# main.net
KiCad netlist of a schematic drawn in Altium Designer
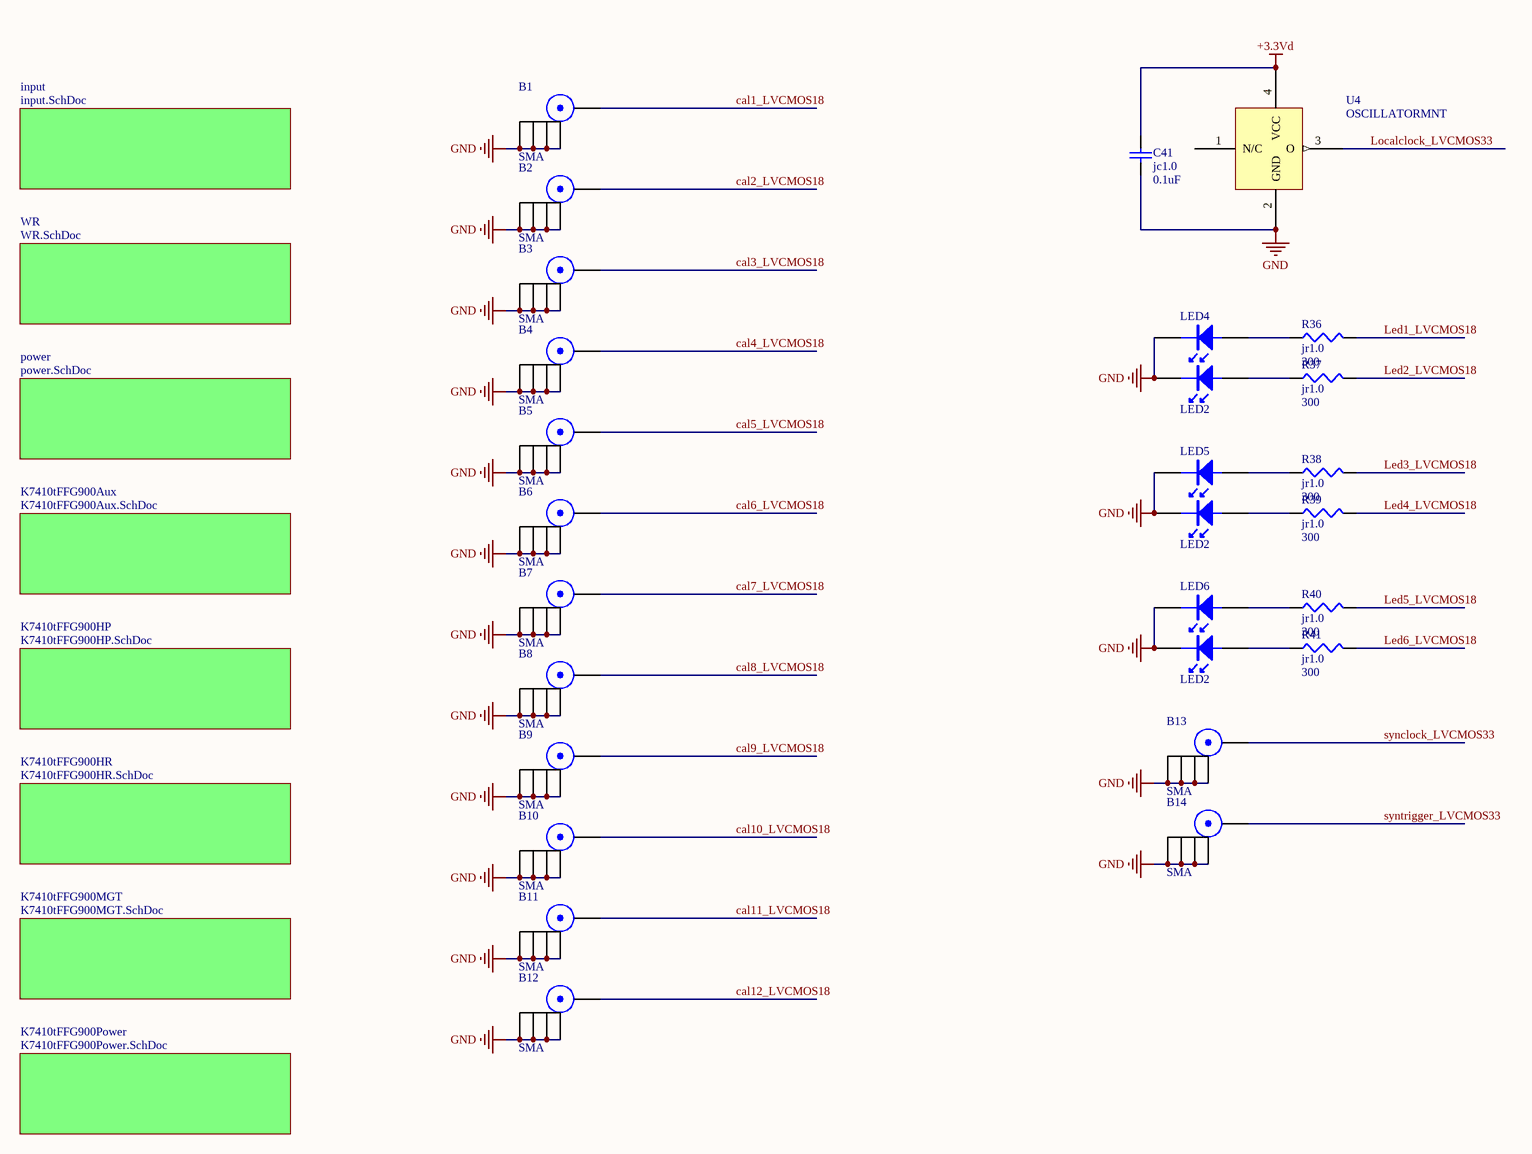
[diagram p0: main.SchDoc]

(export (version "E")
  (design (tool "Eeschema 10.0.6"))
  (components
    (comp (ref "B1") (value "SMA") (footprint "SMA_2") (libsource (lib "LIB01DXP2006SchLib") (part "SMA")))
    (comp (ref "B2") (value "SMA") (footprint "SMA_2") (libsource (lib "LIB01DXP2006SchLib") (part "SMA")))
    (comp (ref "B3") (value "SMA") (footprint "SMA_2") (libsource (lib "LIB01DXP2006SchLib") (part "SMA")))
    (comp (ref "B4") (value "SMA") (footprint "SMA_2") (libsource (lib "LIB01DXP2006SchLib") (part "SMA")))
    (comp (ref "B5") (value "SMA") (footprint "SMA_2") (libsource (lib "LIB01DXP2006SchLib") (part "SMA")))
    (comp (ref "B6") (value "SMA") (footprint "SMA_2") (libsource (lib "LIB01DXP2006SchLib") (part "SMA")))
    (comp (ref "B7") (value "SMA") (footprint "SMA_2") (libsource (lib "LIB01DXP2006SchLib") (part "SMA")))
    (comp (ref "B8") (value "SMA") (footprint "SMA_2") (libsource (lib "LIB01DXP2006SchLib") (part "SMA")))
    (comp (ref "B9") (value "SMA") (footprint "SMA_2") (libsource (lib "LIB01DXP2006SchLib") (part "SMA")))
    (comp (ref "B10") (value "SMA") (footprint "SMA_2") (libsource (lib "LIB01DXP2006SchLib") (part "SMA")))
    (comp (ref "B11") (value "SMA") (footprint "SMA_2") (libsource (lib "LIB01DXP2006SchLib") (part "SMA")))
    (comp (ref "B12") (value "SMA") (footprint "SMA_2") (libsource (lib "LIB01DXP2006SchLib") (part "SMA")))
    (comp (ref "B13") (value "SMA") (footprint "SMA_2") (libsource (lib "LIB01DXP2006SchLib") (part "SMA")))
    (comp (ref "B14") (value "SMA") (footprint "SMA_2") (libsource (lib "LIB01DXP2006SchLib") (part "SMA")))
    (comp (ref "C41")
      (value "jc1.0")
      (footprint "0603")
      (description "Capacitor")
      (fields (field (name "ALTIUM_VALUE") "0.1uF") (field (name "PUBLISHER") "Altium Limited"))
      (libsource (lib "LIB01DXP2006SchLib") (part "Cap"))
    )
    (comp (ref "LED4") (value "LED2") (footprint "LED2") (libsource (lib "LIB01DXP2006SchLib") (part "LED2")))
    (comp (ref "LED5") (value "LED2") (footprint "LED2") (libsource (lib "LIB01DXP2006SchLib") (part "LED2")))
    (comp (ref "LED6") (value "LED2") (footprint "LED2") (libsource (lib "LIB01DXP2006SchLib") (part "LED2")))
    (comp (ref "R36")
      (value "jr1.0")
      (footprint "0805")
      (description "Resistor")
      (fields (field (name "ALTIUM_VALUE") "300") (field (name "PUBLISHER") "Altium Limited"))
      (libsource (lib "LIB01DXP2006SchLib") (part "Res"))
    )
    (comp (ref "R37")
      (value "jr1.0")
      (footprint "0805")
      (description "Resistor")
      (fields (field (name "ALTIUM_VALUE") "300") (field (name "PUBLISHER") "Altium Limited"))
      (libsource (lib "LIB01DXP2006SchLib") (part "Res"))
    )
    (comp (ref "R38")
      (value "jr1.0")
      (footprint "0805")
      (description "Resistor")
      (fields (field (name "ALTIUM_VALUE") "300") (field (name "PUBLISHER") "Altium Limited"))
      (libsource (lib "LIB01DXP2006SchLib") (part "Res"))
    )
    (comp (ref "R39")
      (value "jr1.0")
      (footprint "0805")
      (description "Resistor")
      (fields (field (name "ALTIUM_VALUE") "300") (field (name "PUBLISHER") "Altium Limited"))
      (libsource (lib "LIB01DXP2006SchLib") (part "Res"))
    )
    (comp (ref "R40")
      (value "jr1.0")
      (footprint "0805")
      (description "Resistor")
      (fields (field (name "ALTIUM_VALUE") "300") (field (name "PUBLISHER") "Altium Limited"))
      (libsource (lib "LIB01DXP2006SchLib") (part "Res"))
    )
    (comp (ref "R41")
      (value "jr1.0")
      (footprint "0805")
      (description "Resistor")
      (fields (field (name "ALTIUM_VALUE") "300") (field (name "PUBLISHER") "Altium Limited"))
      (libsource (lib "LIB01DXP2006SchLib") (part "Res"))
    )
    (comp (ref "U4")
      (value "OSCILLATORMNT")
      (footprint "S11")
      (libsource (lib "LIB01DXP2006SchLib") (part "OSCILLATOR"))
    )
  )
  (nets
    (net (code "1") (name "+3.3Vd") (class "Default")
      (node (ref "C41") (pin "2") (pinfunction "2_2") (pintype "passive"))
      (node (ref "U4") (pin "4") (pinfunction "VCC_4") (pintype "power_in"))
    )
    (net (code "2") (name "/Led1_LVCMOS18") (class "Default")
      (node (ref "R36") (pin "2") (pinfunction "2_2") (pintype "passive"))
    )
    (net (code "3") (name "/Led2_LVCMOS18") (class "Default")
      (node (ref "R37") (pin "2") (pinfunction "2_2") (pintype "passive"))
    )
    (net (code "4") (name "/Led3_LVCMOS18") (class "Default")
      (node (ref "R38") (pin "2") (pinfunction "2_2") (pintype "passive"))
    )
    (net (code "5") (name "/Led4_LVCMOS18") (class "Default")
      (node (ref "R39") (pin "2") (pinfunction "2_2") (pintype "passive"))
    )
    (net (code "6") (name "/Led5_LVCMOS18") (class "Default")
      (node (ref "R40") (pin "2") (pinfunction "2_2") (pintype "passive"))
    )
    (net (code "7") (name "/Led6_LVCMOS18") (class "Default")
      (node (ref "R41") (pin "2") (pinfunction "2_2") (pintype "passive"))
    )
    (net (code "8") (name "/Localclock_LVCMOS33") (class "Default")
      (node (ref "U4") (pin "3") (pinfunction "O_3") (pintype "output"))
    )
    (net (code "9") (name "/cal1_LVCMOS18") (class "Default")
      (node (ref "B1") (pin "1") (pinfunction "X_1") (pintype "passive"))
    )
    (net (code "10") (name "/cal2_LVCMOS18") (class "Default")
      (node (ref "B2") (pin "1") (pinfunction "X_1") (pintype "passive"))
    )
    (net (code "11") (name "/cal3_LVCMOS18") (class "Default")
      (node (ref "B3") (pin "1") (pinfunction "X_1") (pintype "passive"))
    )
    (net (code "12") (name "/cal4_LVCMOS18") (class "Default")
      (node (ref "B4") (pin "1") (pinfunction "X_1") (pintype "passive"))
    )
    (net (code "13") (name "/cal5_LVCMOS18") (class "Default")
      (node (ref "B5") (pin "1") (pinfunction "X_1") (pintype "passive"))
    )
    (net (code "14") (name "/cal6_LVCMOS18") (class "Default")
      (node (ref "B6") (pin "1") (pinfunction "X_1") (pintype "passive"))
    )
    (net (code "15") (name "/cal7_LVCMOS18") (class "Default")
      (node (ref "B7") (pin "1") (pinfunction "X_1") (pintype "passive"))
    )
    (net (code "16") (name "/cal8_LVCMOS18") (class "Default")
      (node (ref "B8") (pin "1") (pinfunction "X_1") (pintype "passive"))
    )
    (net (code "17") (name "/cal9_LVCMOS18") (class "Default")
      (node (ref "B9") (pin "1") (pinfunction "X_1") (pintype "passive"))
    )
    (net (code "18") (name "/cal10_LVCMOS18") (class "Default")
      (node (ref "B10") (pin "1") (pinfunction "X_1") (pintype "passive"))
    )
    (net (code "19") (name "/cal11_LVCMOS18") (class "Default")
      (node (ref "B11") (pin "1") (pinfunction "X_1") (pintype "passive"))
    )
    (net (code "20") (name "/cal12_LVCMOS18") (class "Default")
      (node (ref "B12") (pin "1") (pinfunction "X_1") (pintype "passive"))
    )
    (net (code "21") (name "/synclock_LVCMOS33") (class "Default")
      (node (ref "B13") (pin "1") (pinfunction "X_1") (pintype "passive"))
    )
    (net (code "22") (name "/syntrigger_LVCMOS33") (class "Default")
      (node (ref "B14") (pin "1") (pinfunction "X_1") (pintype "passive"))
    )
    (net (code "23") (name "GND") (class "Default")
      (node (ref "B1") (pin "2") (pinfunction "GND_2") (pintype "passive"))
      (node (ref "B1") (pin "3") (pinfunction "GND_3") (pintype "passive"))
      (node (ref "B1") (pin "4") (pinfunction "GND_4") (pintype "passive"))
      (node (ref "B1") (pin "5") (pinfunction "GND_5") (pintype "passive"))
      (node (ref "B10") (pin "2") (pinfunction "GND_2") (pintype "passive"))
      (node (ref "B10") (pin "3") (pinfunction "GND_3") (pintype "passive"))
      (node (ref "B10") (pin "4") (pinfunction "GND_4") (pintype "passive"))
      (node (ref "B10") (pin "5") (pinfunction "GND_5") (pintype "passive"))
      (node (ref "B11") (pin "2") (pinfunction "GND_2") (pintype "passive"))
      (node (ref "B11") (pin "3") (pinfunction "GND_3") (pintype "passive"))
      (node (ref "B11") (pin "4") (pinfunction "GND_4") (pintype "passive"))
      (node (ref "B11") (pin "5") (pinfunction "GND_5") (pintype "passive"))
      (node (ref "B12") (pin "2") (pinfunction "GND_2") (pintype "passive"))
      (node (ref "B12") (pin "3") (pinfunction "GND_3") (pintype "passive"))
      (node (ref "B12") (pin "4") (pinfunction "GND_4") (pintype "passive"))
      (node (ref "B12") (pin "5") (pinfunction "GND_5") (pintype "passive"))
      (node (ref "B13") (pin "2") (pinfunction "GND_2") (pintype "passive"))
      (node (ref "B13") (pin "3") (pinfunction "GND_3") (pintype "passive"))
      (node (ref "B13") (pin "4") (pinfunction "GND_4") (pintype "passive"))
      (node (ref "B13") (pin "5") (pinfunction "GND_5") (pintype "passive"))
      (node (ref "B14") (pin "2") (pinfunction "GND_2") (pintype "passive"))
      (node (ref "B14") (pin "3") (pinfunction "GND_3") (pintype "passive"))
      (node (ref "B14") (pin "4") (pinfunction "GND_4") (pintype "passive"))
      (node (ref "B14") (pin "5") (pinfunction "GND_5") (pintype "passive"))
      (node (ref "B2") (pin "2") (pinfunction "GND_2") (pintype "passive"))
      (node (ref "B2") (pin "3") (pinfunction "GND_3") (pintype "passive"))
      (node (ref "B2") (pin "4") (pinfunction "GND_4") (pintype "passive"))
      (node (ref "B2") (pin "5") (pinfunction "GND_5") (pintype "passive"))
      (node (ref "B3") (pin "2") (pinfunction "GND_2") (pintype "passive"))
      (node (ref "B3") (pin "3") (pinfunction "GND_3") (pintype "passive"))
      (node (ref "B3") (pin "4") (pinfunction "GND_4") (pintype "passive"))
      (node (ref "B3") (pin "5") (pinfunction "GND_5") (pintype "passive"))
      (node (ref "B4") (pin "2") (pinfunction "GND_2") (pintype "passive"))
      (node (ref "B4") (pin "3") (pinfunction "GND_3") (pintype "passive"))
      (node (ref "B4") (pin "4") (pinfunction "GND_4") (pintype "passive"))
      (node (ref "B4") (pin "5") (pinfunction "GND_5") (pintype "passive"))
      (node (ref "B5") (pin "2") (pinfunction "GND_2") (pintype "passive"))
      (node (ref "B5") (pin "3") (pinfunction "GND_3") (pintype "passive"))
      (node (ref "B5") (pin "4") (pinfunction "GND_4") (pintype "passive"))
      (node (ref "B5") (pin "5") (pinfunction "GND_5") (pintype "passive"))
      (node (ref "B6") (pin "2") (pinfunction "GND_2") (pintype "passive"))
      (node (ref "B6") (pin "3") (pinfunction "GND_3") (pintype "passive"))
      (node (ref "B6") (pin "4") (pinfunction "GND_4") (pintype "passive"))
      (node (ref "B6") (pin "5") (pinfunction "GND_5") (pintype "passive"))
      (node (ref "B7") (pin "2") (pinfunction "GND_2") (pintype "passive"))
      (node (ref "B7") (pin "3") (pinfunction "GND_3") (pintype "passive"))
      (node (ref "B7") (pin "4") (pinfunction "GND_4") (pintype "passive"))
      (node (ref "B7") (pin "5") (pinfunction "GND_5") (pintype "passive"))
      (node (ref "B8") (pin "2") (pinfunction "GND_2") (pintype "passive"))
      (node (ref "B8") (pin "3") (pinfunction "GND_3") (pintype "passive"))
      (node (ref "B8") (pin "4") (pinfunction "GND_4") (pintype "passive"))
      (node (ref "B8") (pin "5") (pinfunction "GND_5") (pintype "passive"))
      (node (ref "B9") (pin "2") (pinfunction "GND_2") (pintype "passive"))
      (node (ref "B9") (pin "3") (pinfunction "GND_3") (pintype "passive"))
      (node (ref "B9") (pin "4") (pinfunction "GND_4") (pintype "passive"))
      (node (ref "B9") (pin "5") (pinfunction "GND_5") (pintype "passive"))
      (node (ref "C41") (pin "1") (pinfunction "1_1") (pintype "passive"))
      (node (ref "LED4") (pin "2") (pinfunction "2_2") (pintype "passive"))
      (node (ref "LED4") (pin "4") (pinfunction "4_4") (pintype "passive"))
      (node (ref "LED5") (pin "2") (pinfunction "2_2") (pintype "passive"))
      (node (ref "LED5") (pin "4") (pinfunction "4_4") (pintype "passive"))
      (node (ref "LED6") (pin "2") (pinfunction "2_2") (pintype "passive"))
      (node (ref "LED6") (pin "4") (pinfunction "4_4") (pintype "passive"))
      (node (ref "U4") (pin "2") (pinfunction "GND_2") (pintype "passive"))
    )
    (net (code "24") (name "Net-(LED4-Pad1)") (class "Default")
      (node (ref "LED4") (pin "1") (pinfunction "1_1") (pintype "passive"))
      (node (ref "R37") (pin "1") (pinfunction "1_1") (pintype "passive"))
    )
    (net (code "25") (name "Net-(LED4-Pad3)") (class "Default")
      (node (ref "LED4") (pin "3") (pinfunction "3_3") (pintype "passive"))
      (node (ref "R36") (pin "1") (pinfunction "1_1") (pintype "passive"))
    )
    (net (code "26") (name "Net-(LED5-Pad1)") (class "Default")
      (node (ref "LED5") (pin "1") (pinfunction "1_1") (pintype "passive"))
      (node (ref "R39") (pin "1") (pinfunction "1_1") (pintype "passive"))
    )
    (net (code "27") (name "Net-(LED5-Pad3)") (class "Default")
      (node (ref "LED5") (pin "3") (pinfunction "3_3") (pintype "passive"))
      (node (ref "R38") (pin "1") (pinfunction "1_1") (pintype "passive"))
    )
    (net (code "28") (name "Net-(LED6-Pad1)") (class "Default")
      (node (ref "LED6") (pin "1") (pinfunction "1_1") (pintype "passive"))
      (node (ref "R41") (pin "1") (pinfunction "1_1") (pintype "passive"))
    )
    (net (code "29") (name "Net-(LED6-Pad3)") (class "Default")
      (node (ref "LED6") (pin "3") (pinfunction "3_3") (pintype "passive"))
      (node (ref "R40") (pin "1") (pinfunction "1_1") (pintype "passive"))
    )
    (net (code "30") (name "unconnected-(U4-N{slash}C-Pad1)") (class "Default")
      (node (ref "U4") (pin "1") (pinfunction "N/C_1") (pintype "passive"))
    )
  )
)
